# mechanical.net
KiCad netlist of a schematic drawn in Altium Designer
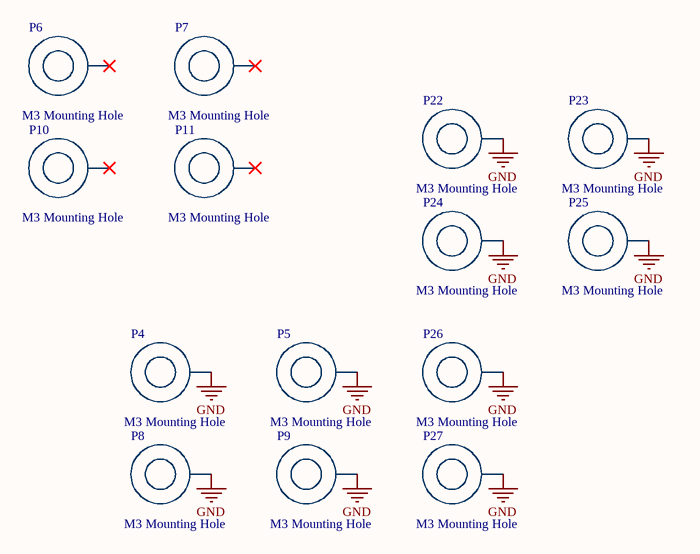
[diagram p0: mechanical.SchDoc]

(export (version "E")
  (design (tool "Eeschema 10.0.6"))
  (components
    (comp (ref "P4")
      (value "M3 Mounting Hole")
      (footprint "MH-M3")
      (libsource (lib "Arturo_Approved") (part "MH-M3"))
    )
    (comp (ref "P5")
      (value "M3 Mounting Hole")
      (footprint "MH-M3")
      (libsource (lib "Arturo_Approved") (part "MH-M3"))
    )
    (comp (ref "P6")
      (value "M3 Mounting Hole")
      (footprint "MH-M3")
      (libsource (lib "Arturo_Approved") (part "MH-M3"))
    )
    (comp (ref "P7")
      (value "M3 Mounting Hole")
      (footprint "MH-M3")
      (libsource (lib "Arturo_Approved") (part "MH-M3"))
    )
    (comp (ref "P8")
      (value "M3 Mounting Hole")
      (footprint "MH-M3")
      (libsource (lib "Arturo_Approved") (part "MH-M3"))
    )
    (comp (ref "P9")
      (value "M3 Mounting Hole")
      (footprint "MH-M3")
      (libsource (lib "Arturo_Approved") (part "MH-M3"))
    )
    (comp (ref "P10")
      (value "M3 Mounting Hole")
      (footprint "MH-M3")
      (libsource (lib "Arturo_Approved") (part "MH-M3"))
    )
    (comp (ref "P11")
      (value "M3 Mounting Hole")
      (footprint "MH-M3")
      (libsource (lib "Arturo_Approved") (part "MH-M3"))
    )
    (comp (ref "P22")
      (value "M3 Mounting Hole")
      (footprint "MH-M3")
      (libsource (lib "Arturo_Approved") (part "MH-M3"))
    )
    (comp (ref "P23")
      (value "M3 Mounting Hole")
      (footprint "MH-M3")
      (libsource (lib "Arturo_Approved") (part "MH-M3"))
    )
    (comp (ref "P24")
      (value "M3 Mounting Hole")
      (footprint "MH-M3")
      (libsource (lib "Arturo_Approved") (part "MH-M3"))
    )
    (comp (ref "P25")
      (value "M3 Mounting Hole")
      (footprint "MH-M3")
      (libsource (lib "Arturo_Approved") (part "MH-M3"))
    )
    (comp (ref "P26")
      (value "M3 Mounting Hole")
      (footprint "MH-M3")
      (libsource (lib "Arturo_Approved") (part "MH-M3"))
    )
    (comp (ref "P27")
      (value "M3 Mounting Hole")
      (footprint "MH-M3")
      (libsource (lib "Arturo_Approved") (part "MH-M3"))
    )
  )
  (nets
    (net (code "1") (name "GND") (class "Default")
      (node (ref "P22") (pin "1") (pinfunction "1_1") (pintype "passive"))
      (node (ref "P23") (pin "1") (pinfunction "1_1") (pintype "passive"))
      (node (ref "P24") (pin "1") (pinfunction "1_1") (pintype "passive"))
      (node (ref "P25") (pin "1") (pinfunction "1_1") (pintype "passive"))
      (node (ref "P26") (pin "1") (pinfunction "1_1") (pintype "passive"))
      (node (ref "P27") (pin "1") (pinfunction "1_1") (pintype "passive"))
      (node (ref "P4") (pin "1") (pinfunction "1_1") (pintype "passive"))
      (node (ref "P5") (pin "1") (pinfunction "1_1") (pintype "passive"))
      (node (ref "P8") (pin "1") (pinfunction "1_1") (pintype "passive"))
      (node (ref "P9") (pin "1") (pinfunction "1_1") (pintype "passive"))
    )
    (net (code "2") (name "unconnected-(P6-Pad1)") (class "Default")
      (node (ref "P6") (pin "1") (pinfunction "1_1") (pintype "passive+no_connect"))
    )
    (net (code "3") (name "unconnected-(P7-Pad1)") (class "Default")
      (node (ref "P7") (pin "1") (pinfunction "1_1") (pintype "passive+no_connect"))
    )
    (net (code "4") (name "unconnected-(P10-Pad1)") (class "Default")
      (node (ref "P10") (pin "1") (pinfunction "1_1") (pintype "passive+no_connect"))
    )
    (net (code "5") (name "unconnected-(P11-Pad1)") (class "Default")
      (node (ref "P11") (pin "1") (pinfunction "1_1") (pintype "passive+no_connect"))
    )
  )
)
